# MCU_Interconnect_Rev1.net
KiCad netlist of a schematic drawn in Altium Designer
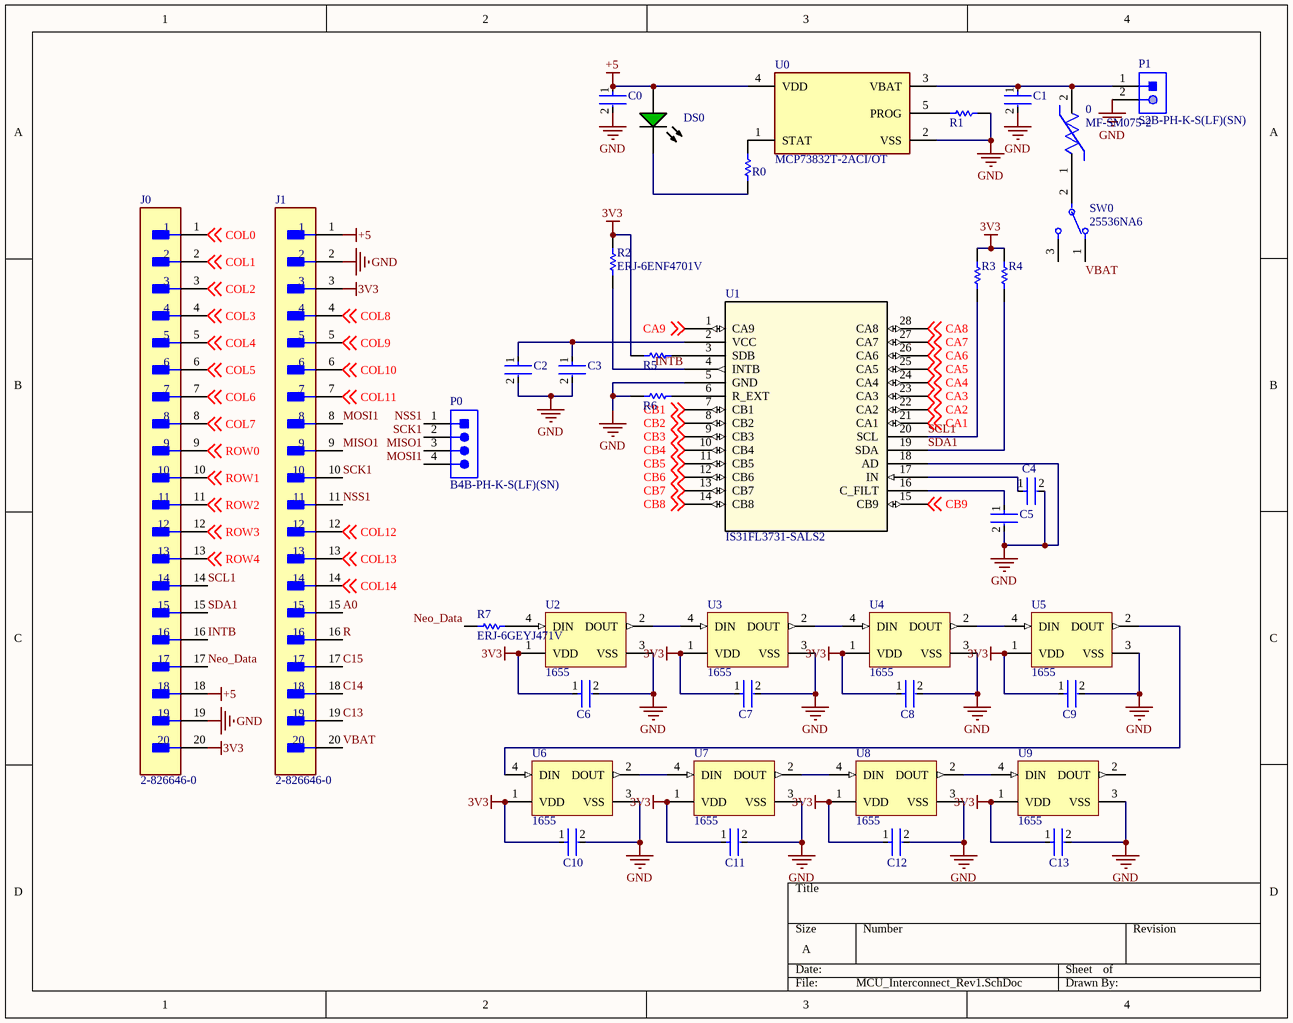
[diagram p0: MCU_Interconnect_Rev1.SchDoc]

(export (version "E")
  (design (tool "Eeschema 10.0.6"))
  (components
    (comp (ref "0")
      (value "MF-SM075-2")
      (footprint "FP-MF-SM075-MFG")
      (description "Polymeric PTC Resettable Fuse 30V 750mA Ih Surface Mount 2-SMD")
      (fields (field (name "MANUFACTURER") "Bourns Inc."))
      (libsource (lib "Altium Content Vault") (part "fdf083d5f6389a9a1c4e51137f46658"))
    )
    (comp (ref "C0")
      (value "GRM21BR71C475KE51L")
      (footprint "FP-GRM21B-0_15-IPC_C")
      (description "Chip Multilayer Ceramic Capacitors for General Purpose, 0805, 4.7uF, X7R, 15%, 10%, 16V")
      (fields (field (name "TOLERANCE") "10%"))
      (libsource (lib "Altium Content Vault") (part "b4654b650e69147ec39a6b967a45e02"))
    )
    (comp (ref "C1")
      (value "GRM21BR71C475KE51L")
      (footprint "FP-GRM21B-0_15-IPC_C")
      (description "Chip Multilayer Ceramic Capacitors for General Purpose, 0805, 4.7uF, X7R, 15%, 10%, 16V")
      (fields (field (name "TOLERANCE") "10%"))
      (libsource (lib "Altium Content Vault") (part "b4654b650e69147ec39a6b967a45e02"))
    )
    (comp (ref "C2")
      (value "GRM219R7YA105KA12D")
      (footprint "FP-GRM219-0_1-MFG")
      (description "Chip Multilayer Ceramic Capacitors for General Purpose, 0805, 1.0uF, X7R, 15%, 10%, 35V")
      (fields (field (name "TOLERANCE") "10%"))
      (libsource (lib "Altium Content Vault") (part "02cd4be3c70576c341d710602a673aa"))
    )
    (comp (ref "C3")
      (value "GRM21B7U1A104JA01L")
      (footprint "FP-GRM21B-0_1-IPC_B")
      (description "Chip Multilayer Ceramic Capacitors for General Purpose, 0805, 0.10uF, U2J, -750ppm/°C, 5%, 10V")
      (fields (field (name "TOLERANCE") "5%"))
      (libsource (lib "Altium Content Vault") (part "b4654b650e69147ec39a6b967a45e02"))
    )
    (comp (ref "C4")
      (value "GCM21BR71H224KA37L")
      (footprint "FP-GCM21B-0_15-IPC_C")
      (description "Ceramic Capacitor for Automotive 220nF ±10% 50VDC X7R 0805 Embossed T/R")
      (fields (field (name "TOLERANCE") "10%") (field (name "VOLTAGE") "50V"))
      (libsource (lib "Altium Content Vault") (part "02cd4be3c70576c341d710602a673aa"))
    )
    (comp (ref "C5")
      (value "GRM21B7U1A104JA01L")
      (footprint "FP-GRM21B-0_1-IPC_B")
      (description "Chip Multilayer Ceramic Capacitors for General Purpose, 0805, 0.10uF, U2J, -750ppm/°C, 5%, 10V")
      (fields (field (name "TOLERANCE") "5%"))
      (libsource (lib "Altium Content Vault") (part "b4654b650e69147ec39a6b967a45e02"))
    )
    (comp (ref "C6")
      (value "GRM21B7U1A104JA01L")
      (footprint "FP-GRM21B-0_1-IPC_B")
      (description "Chip Multilayer Ceramic Capacitors for General Purpose, 0805, 0.10uF, U2J, -750ppm/°C, 5%, 10V")
      (fields (field (name "TOLERANCE") "5%"))
      (libsource (lib "Altium Content Vault") (part "b4654b650e69147ec39a6b967a45e02"))
    )
    (comp (ref "C7")
      (value "GRM21B7U1A104JA01L")
      (footprint "FP-GRM21B-0_1-IPC_B")
      (description "Chip Multilayer Ceramic Capacitors for General Purpose, 0805, 0.10uF, U2J, -750ppm/°C, 5%, 10V")
      (fields (field (name "TOLERANCE") "5%"))
      (libsource (lib "Altium Content Vault") (part "b4654b650e69147ec39a6b967a45e02"))
    )
    (comp (ref "C8")
      (value "GRM21B7U1A104JA01L")
      (footprint "FP-GRM21B-0_1-IPC_B")
      (description "Chip Multilayer Ceramic Capacitors for General Purpose, 0805, 0.10uF, U2J, -750ppm/°C, 5%, 10V")
      (fields (field (name "TOLERANCE") "5%"))
      (libsource (lib "Altium Content Vault") (part "b4654b650e69147ec39a6b967a45e02"))
    )
    (comp (ref "C9")
      (value "GRM21B7U1A104JA01L")
      (footprint "FP-GRM21B-0_1-IPC_B")
      (description "Chip Multilayer Ceramic Capacitors for General Purpose, 0805, 0.10uF, U2J, -750ppm/°C, 5%, 10V")
      (fields (field (name "TOLERANCE") "5%"))
      (libsource (lib "Altium Content Vault") (part "b4654b650e69147ec39a6b967a45e02"))
    )
    (comp (ref "C10")
      (value "GRM21B7U1A104JA01L")
      (footprint "FP-GRM21B-0_1-IPC_B")
      (description "Chip Multilayer Ceramic Capacitors for General Purpose, 0805, 0.10uF, U2J, -750ppm/°C, 5%, 10V")
      (fields (field (name "TOLERANCE") "5%"))
      (libsource (lib "Altium Content Vault") (part "b4654b650e69147ec39a6b967a45e02"))
    )
    (comp (ref "C11")
      (value "GRM21B7U1A104JA01L")
      (footprint "FP-GRM21B-0_1-IPC_B")
      (description "Chip Multilayer Ceramic Capacitors for General Purpose, 0805, 0.10uF, U2J, -750ppm/°C, 5%, 10V")
      (fields (field (name "TOLERANCE") "5%"))
      (libsource (lib "Altium Content Vault") (part "b4654b650e69147ec39a6b967a45e02"))
    )
    (comp (ref "C12")
      (value "GRM21B7U1A104JA01L")
      (footprint "FP-GRM21B-0_1-IPC_B")
      (description "Chip Multilayer Ceramic Capacitors for General Purpose, 0805, 0.10uF, U2J, -750ppm/°C, 5%, 10V")
      (fields (field (name "TOLERANCE") "5%"))
      (libsource (lib "Altium Content Vault") (part "b4654b650e69147ec39a6b967a45e02"))
    )
    (comp (ref "C13")
      (value "GRM21B7U1A104JA01L")
      (footprint "FP-GRM21B-0_1-IPC_B")
      (description "Chip Multilayer Ceramic Capacitors for General Purpose, 0805, 0.10uF, U2J, -750ppm/°C, 5%, 10V")
      (fields (field (name "TOLERANCE") "5%"))
      (libsource (lib "Altium Content Vault") (part "b4654b650e69147ec39a6b967a45e02"))
    )
    (comp (ref "DS0")
      (value "LTST-C170KGKT")
      (footprint "LTST-LTST-C170KGKT-2_V")
      (description "Ultra Bright AlInGaP Chip LED, 75 mW, -55 to 85 degC, 2-Pin SMD (0805), RoHS, Tape and Reel")
      (fields (field (name "MANUFACTURER") "Lite-On"))
      (libsource (lib "Altium Content Vault") (part "LED-GREEN-KA-2"))
    )
    (comp (ref "J0")
      (value "2-826646-0")
      (footprint "FP-2-826646-0-MFG")
      (description "CONN HEADER VERT 20POS 2.54MM")
      (libsource (lib "Altium Content Vault") (part "09d5f2461bb0697fba3bd732061644e"))
    )
    (comp (ref "J1")
      (value "2-826646-0")
      (footprint "FP-2-826646-0-MFG")
      (description "CONN HEADER VERT 20POS 2.54MM")
      (libsource (lib "Altium Content Vault") (part "09d5f2461bb0697fba3bd732061644e"))
    )
    (comp (ref "P0")
      (value "B4B-PH-K-S(LF)(SN)")
      (footprint "JST-B4B-PH-K-S_V")
      (fields (field (name "MANUFACTURER") "JST"))
      (libsource (lib "Altium Content Vault") (part "CN-1P-M-R4"))
    )
    (comp (ref "P1")
      (value "S2B-PH-K-S(LF)(SN)")
      (footprint "JST-S2B-PH-K-S_V")
      (fields (field (name "TOLERANCE") "20%"))
      (libsource (lib "Altium Content Vault") (part "CN-1P-M-R2"))
    )
    (comp (ref "R0")
      (value "RC0805FR-07470RL")
      (footprint "RESC2013X60X35LL10T20")
      (description "Chip Resistor, 470 Ohm, +/- 1%, 125 mW, -55 to 155 degC, 0805 (2012 Metric), RoHS, Tape and Reel")
      (fields (field (name "MANUFACTURER") "Yageo"))
      (libsource (lib "Altium Content Vault") (part "RES-2"))
    )
    (comp (ref "R1")
      (value "ERJ-6ENF1001V")
      (footprint "RESC2013X70X40ML20T20")
      (description "Chip Resistor, 1 KOhm, +/- 1%, 0.125 W, -55 to 155 degC, 0805 (2012 Metric), RoHS, Tape and Reel")
      (fields (field (name "MANUFACTURER") "Panasonic"))
      (libsource (lib "Altium Content Vault") (part "RES-2"))
    )
    (comp (ref "R2")
      (value "ERJ-6ENF4701V")
      (footprint "RESC2013X70X40NL20T20")
      (description "Chip Resistor, 4.7 KOhm, +/- 1%, 0.125 W, -55 to 155 degC, 0805 (2012 Metric), RoHS, Tape and Reel")
      (fields (field (name "MANUFACTURER") "Panasonic"))
      (libsource (lib "Altium Content Vault") (part "RES-2"))
    )
    (comp (ref "R3")
      (value "ERJ-6ENF4701V")
      (footprint "RESC2013X70X40NL20T20")
      (description "Chip Resistor, 4.7 KOhm, +/- 1%, 0.125 W, -55 to 155 degC, 0805 (2012 Metric), RoHS, Tape and Reel")
      (fields (field (name "MANUFACTURER") "Panasonic"))
      (libsource (lib "Altium Content Vault") (part "RES-2"))
    )
    (comp (ref "R4")
      (value "ERJ-6ENF4701V")
      (footprint "RESC2013X70X40NL20T20")
      (description "Chip Resistor, 4.7 KOhm, +/- 1%, 0.125 W, -55 to 155 degC, 0805 (2012 Metric), RoHS, Tape and Reel")
      (fields (field (name "MANUFACTURER") "Panasonic"))
      (libsource (lib "Altium Content Vault") (part "RES-2"))
    )
    (comp (ref "R5")
      (value "ERJ-6ENF1003V")
      (footprint "RESC2013X70X40ML20T20")
      (description "100kOhm")
      (fields (field (name "MANUFACTURER") "Panasonic"))
      (libsource (lib "Altium Content Vault") (part "RES"))
    )
    (comp (ref "R6")
      (value "ERJ-6ENF1003V")
      (footprint "RESC2013X70X40ML20T20")
      (description "100kOhm")
      (fields (field (name "MANUFACTURER") "Panasonic"))
      (libsource (lib "Altium Content Vault") (part "RES"))
    )
    (comp (ref "R7")
      (value "ERJ-6GEYJ471V")
      (footprint "RESC2013X70X40LL20T20")
      (fields (field (name "MANUFACTURER") "Panasonic"))
      (libsource (lib "Altium Content Vault") (part "RES"))
    )
    (comp (ref "SW0")
      (value "25536NA6")
      (footprint "FP-25536NA6-0")
      (description "SWITCH SLIDE SPDT 4A 125V")
      (libsource (lib "Altium Content Vault") (part "52c419afdc2a387c7d548259a9aeefb"))
    )
    (comp (ref "U0")
      (value "MCP73832T-2ACI/OT")
      (footprint "FP-C04-091-OT-MFG")
      (description "IC LI-ION/LI-POLY CTRLR SOT23-5")
      (libsource (lib "Altium Content Vault") (part "61f5a3bb3429d9e0caadea342aa3b19"))
    )
    (comp (ref "U1")
      (value "IS31FL3731-SALS2")
      (footprint "SSOP-28_ISI")
      (description "No Description Available")
      (fields (field (name "COPYRIGHT") "Copyright (C) 2018 Accelerated Designs. All rights reserved"))
      (libsource (lib "IS31FL3731-SALS2") (part "IS31FL3731-SALS2"))
    )
    (comp (ref "U2")
      (value "1655")
      (footprint "ADA-RGB-1655_V")
      (fields (field (name "MANUFACTURER") "Adafruit-Industries-LLC"))
      (libsource (lib "Altium Content Vault") (part "ADA-RGB-1655-4"))
    )
    (comp (ref "U3")
      (value "1655")
      (footprint "ADA-RGB-1655_V")
      (fields (field (name "MANUFACTURER") "Adafruit-Industries-LLC"))
      (libsource (lib "Altium Content Vault") (part "ADA-RGB-1655-4"))
    )
    (comp (ref "U4")
      (value "1655")
      (footprint "ADA-RGB-1655_V")
      (fields (field (name "MANUFACTURER") "Adafruit-Industries-LLC"))
      (libsource (lib "Altium Content Vault") (part "ADA-RGB-1655-4"))
    )
    (comp (ref "U5")
      (value "1655")
      (footprint "ADA-RGB-1655_V")
      (fields (field (name "MANUFACTURER") "Adafruit-Industries-LLC"))
      (libsource (lib "Altium Content Vault") (part "ADA-RGB-1655-4"))
    )
    (comp (ref "U6")
      (value "1655")
      (footprint "ADA-RGB-1655_V")
      (fields (field (name "MANUFACTURER") "Adafruit-Industries-LLC"))
      (libsource (lib "Altium Content Vault") (part "ADA-RGB-1655-4"))
    )
    (comp (ref "U7")
      (value "1655")
      (footprint "ADA-RGB-1655_V")
      (fields (field (name "MANUFACTURER") "Adafruit-Industries-LLC"))
      (libsource (lib "Altium Content Vault") (part "ADA-RGB-1655-4"))
    )
    (comp (ref "U8")
      (value "1655")
      (footprint "ADA-RGB-1655_V")
      (fields (field (name "MANUFACTURER") "Adafruit-Industries-LLC"))
      (libsource (lib "Altium Content Vault") (part "ADA-RGB-1655-4"))
    )
    (comp (ref "U9")
      (value "1655")
      (footprint "ADA-RGB-1655_V")
      (fields (field (name "MANUFACTURER") "Adafruit-Industries-LLC"))
      (libsource (lib "Altium Content Vault") (part "ADA-RGB-1655-4"))
    )
  )
  (nets
    (net (code "1") (name "+5") (class "Default")
      (node (ref "C0") (pin "1") (pinfunction "1_1") (pintype "passive"))
      (node (ref "DS0") (pin "2") (pinfunction "A_2") (pintype "passive"))
      (node (ref "J0") (pin "18") (pinfunction "18_18") (pintype "passive"))
      (node (ref "J1") (pin "1") (pinfunction "1_1") (pintype "passive"))
      (node (ref "U0") (pin "4") (pinfunction "VDD_4") (pintype "power_in"))
    )
    (net (code "2") (name "/A0") (class "Default")
      (node (ref "J1") (pin "15") (pinfunction "15_15") (pintype "passive"))
    )
    (net (code "3") (name "/C13") (class "Default")
      (node (ref "J1") (pin "19") (pinfunction "19_19") (pintype "passive"))
    )
    (net (code "4") (name "/C14") (class "Default")
      (node (ref "J1") (pin "18") (pinfunction "18_18") (pintype "passive"))
    )
    (net (code "5") (name "/C15") (class "Default")
      (node (ref "J1") (pin "17") (pinfunction "17_17") (pintype "passive"))
    )
    (net (code "6") (name "/INTB") (class "Default")
      (node (ref "J0") (pin "16") (pinfunction "16_16") (pintype "passive"))
      (node (ref "R2") (pin "1") (pinfunction "1_1") (pintype "passive"))
      (node (ref "U1") (pin "4") (pinfunction "INTB_4") (pintype "output"))
    )
    (net (code "7") (name "/MISO1") (class "Default")
      (node (ref "J1") (pin "9") (pinfunction "9_9") (pintype "passive"))
      (node (ref "P0") (pin "3") (pinfunction "3_3") (pintype "passive"))
    )
    (net (code "8") (name "/MOSI1") (class "Default")
      (node (ref "J1") (pin "8") (pinfunction "8_8") (pintype "passive"))
      (node (ref "P0") (pin "4") (pinfunction "4_4") (pintype "passive"))
    )
    (net (code "9") (name "/NSS1") (class "Default")
      (node (ref "J1") (pin "11") (pinfunction "11_11") (pintype "passive"))
      (node (ref "P0") (pin "1") (pinfunction "1_1") (pintype "passive"))
    )
    (net (code "10") (name "/Neo_Data") (class "Default")
      (node (ref "J0") (pin "17") (pinfunction "17_17") (pintype "passive"))
      (node (ref "R7") (pin "1") (pinfunction "1_1") (pintype "passive"))
    )
    (net (code "11") (name "/R") (class "Default")
      (node (ref "J1") (pin "16") (pinfunction "16_16") (pintype "passive"))
    )
    (net (code "12") (name "/SCK1") (class "Default")
      (node (ref "J1") (pin "10") (pinfunction "10_10") (pintype "passive"))
      (node (ref "P0") (pin "2") (pinfunction "2_2") (pintype "passive"))
    )
    (net (code "13") (name "/SCL1") (class "Default")
      (node (ref "J0") (pin "14") (pinfunction "14_14") (pintype "passive"))
      (node (ref "R3") (pin "1") (pinfunction "1_1") (pintype "passive"))
      (node (ref "U1") (pin "20") (pinfunction "SCL_20") (pintype "passive"))
    )
    (net (code "14") (name "/SDA1") (class "Default")
      (node (ref "J0") (pin "15") (pinfunction "15_15") (pintype "passive"))
      (node (ref "R4") (pin "1") (pinfunction "1_1") (pintype "passive"))
      (node (ref "U1") (pin "19") (pinfunction "SDA_19") (pintype "passive"))
    )
    (net (code "15") (name "/VBAT") (class "Default")
      (node (ref "J1") (pin "20") (pinfunction "20_20") (pintype "passive"))
      (node (ref "SW0") (pin "1") (pinfunction "1_1") (pintype "passive"))
    )
    (net (code "16") (name "3V3") (class "Default")
      (node (ref "C10") (pin "1") (pinfunction "1_1") (pintype "passive"))
      (node (ref "C11") (pin "1") (pinfunction "1_1") (pintype "passive"))
      (node (ref "C12") (pin "1") (pinfunction "1_1") (pintype "passive"))
      (node (ref "C13") (pin "1") (pinfunction "1_1") (pintype "passive"))
      (node (ref "C6") (pin "1") (pinfunction "1_1") (pintype "passive"))
      (node (ref "C7") (pin "1") (pinfunction "1_1") (pintype "passive"))
      (node (ref "C8") (pin "1") (pinfunction "1_1") (pintype "passive"))
      (node (ref "C9") (pin "1") (pinfunction "1_1") (pintype "passive"))
      (node (ref "J0") (pin "20") (pinfunction "20_20") (pintype "passive"))
      (node (ref "J1") (pin "3") (pinfunction "3_3") (pintype "passive"))
      (node (ref "R2") (pin "2") (pinfunction "2_2") (pintype "passive"))
      (node (ref "R3") (pin "2") (pinfunction "2_2") (pintype "passive"))
      (node (ref "R4") (pin "2") (pinfunction "2_2") (pintype "passive"))
      (node (ref "R5") (pin "1") (pinfunction "1_1") (pintype "passive"))
      (node (ref "U2") (pin "1") (pinfunction "VDD_1") (pintype "power_in"))
      (node (ref "U3") (pin "1") (pinfunction "VDD_1") (pintype "power_in"))
      (node (ref "U4") (pin "1") (pinfunction "VDD_1") (pintype "power_in"))
      (node (ref "U5") (pin "1") (pinfunction "VDD_1") (pintype "power_in"))
      (node (ref "U6") (pin "1") (pinfunction "VDD_1") (pintype "power_in"))
      (node (ref "U7") (pin "1") (pinfunction "VDD_1") (pintype "power_in"))
      (node (ref "U8") (pin "1") (pinfunction "VDD_1") (pintype "power_in"))
      (node (ref "U9") (pin "1") (pinfunction "VDD_1") (pintype "power_in"))
    )
    (net (code "17") (name "CA1") (class "Default")
      (node (ref "U1") (pin "21") (pinfunction "CA1_21") (pintype "bidirectional"))
    )
    (net (code "18") (name "CA2") (class "Default")
      (node (ref "U1") (pin "22") (pinfunction "CA2_22") (pintype "bidirectional"))
    )
    (net (code "19") (name "CA3") (class "Default")
      (node (ref "U1") (pin "23") (pinfunction "CA3_23") (pintype "bidirectional"))
    )
    (net (code "20") (name "CA4") (class "Default")
      (node (ref "U1") (pin "24") (pinfunction "CA4_24") (pintype "bidirectional"))
    )
    (net (code "21") (name "CA5") (class "Default")
      (node (ref "U1") (pin "25") (pinfunction "CA5_25") (pintype "bidirectional"))
    )
    (net (code "22") (name "CA6") (class "Default")
      (node (ref "U1") (pin "26") (pinfunction "CA6_26") (pintype "bidirectional"))
    )
    (net (code "23") (name "CA7") (class "Default")
      (node (ref "U1") (pin "27") (pinfunction "CA7_27") (pintype "bidirectional"))
    )
    (net (code "24") (name "CA8") (class "Default")
      (node (ref "U1") (pin "28") (pinfunction "CA8_28") (pintype "bidirectional"))
    )
    (net (code "25") (name "CA9") (class "Default")
      (node (ref "U1") (pin "1") (pinfunction "CA9_1") (pintype "bidirectional"))
    )
    (net (code "26") (name "CB1") (class "Default")
      (node (ref "U1") (pin "7") (pinfunction "CB1_7") (pintype "bidirectional"))
    )
    (net (code "27") (name "CB2") (class "Default")
      (node (ref "U1") (pin "8") (pinfunction "CB2_8") (pintype "bidirectional"))
    )
    (net (code "28") (name "CB3") (class "Default")
      (node (ref "U1") (pin "9") (pinfunction "CB3_9") (pintype "bidirectional"))
    )
    (net (code "29") (name "CB4") (class "Default")
      (node (ref "U1") (pin "10") (pinfunction "CB4_10") (pintype "bidirectional"))
    )
    (net (code "30") (name "CB5") (class "Default")
      (node (ref "U1") (pin "11") (pinfunction "CB5_11") (pintype "bidirectional"))
    )
    (net (code "31") (name "CB6") (class "Default")
      (node (ref "U1") (pin "12") (pinfunction "CB6_12") (pintype "bidirectional"))
    )
    (net (code "32") (name "CB7") (class "Default")
      (node (ref "U1") (pin "13") (pinfunction "CB7_13") (pintype "bidirectional"))
    )
    (net (code "33") (name "CB8") (class "Default")
      (node (ref "U1") (pin "14") (pinfunction "CB8_14") (pintype "bidirectional"))
    )
    (net (code "34") (name "CB9") (class "Default")
      (node (ref "U1") (pin "15") (pinfunction "CB9_15") (pintype "bidirectional"))
    )
    (net (code "35") (name "COL0") (class "Default")
      (node (ref "J0") (pin "1") (pinfunction "1_1") (pintype "passive"))
    )
    (net (code "36") (name "COL1") (class "Default")
      (node (ref "J0") (pin "2") (pinfunction "2_2") (pintype "passive"))
    )
    (net (code "37") (name "COL2") (class "Default")
      (node (ref "J0") (pin "3") (pinfunction "3_3") (pintype "passive"))
    )
    (net (code "38") (name "COL3") (class "Default")
      (node (ref "J0") (pin "4") (pinfunction "4_4") (pintype "passive"))
    )
    (net (code "39") (name "COL4") (class "Default")
      (node (ref "J0") (pin "5") (pinfunction "5_5") (pintype "passive"))
    )
    (net (code "40") (name "COL5") (class "Default")
      (node (ref "J0") (pin "6") (pinfunction "6_6") (pintype "passive"))
    )
    (net (code "41") (name "COL6") (class "Default")
      (node (ref "J0") (pin "7") (pinfunction "7_7") (pintype "passive"))
    )
    (net (code "42") (name "COL7") (class "Default")
      (node (ref "J0") (pin "8") (pinfunction "8_8") (pintype "passive"))
    )
    (net (code "43") (name "COL8") (class "Default")
      (node (ref "J1") (pin "4") (pinfunction "4_4") (pintype "passive"))
    )
    (net (code "44") (name "COL9") (class "Default")
      (node (ref "J1") (pin "5") (pinfunction "5_5") (pintype "passive"))
    )
    (net (code "45") (name "COL10") (class "Default")
      (node (ref "J1") (pin "6") (pinfunction "6_6") (pintype "passive"))
    )
    (net (code "46") (name "COL11") (class "Default")
      (node (ref "J1") (pin "7") (pinfunction "7_7") (pintype "passive"))
    )
    (net (code "47") (name "COL12") (class "Default")
      (node (ref "J1") (pin "12") (pinfunction "12_12") (pintype "passive"))
    )
    (net (code "48") (name "COL13") (class "Default")
      (node (ref "J1") (pin "13") (pinfunction "13_13") (pintype "passive"))
    )
    (net (code "49") (name "COL14") (class "Default")
      (node (ref "J1") (pin "14") (pinfunction "14_14") (pintype "passive"))
    )
    (net (code "50") (name "GND") (class "Default")
      (node (ref "C0") (pin "2") (pinfunction "2_2") (pintype "passive"))
      (node (ref "C1") (pin "2") (pinfunction "2_2") (pintype "passive"))
      (node (ref "C10") (pin "2") (pinfunction "2_2") (pintype "passive"))
      (node (ref "C11") (pin "2") (pinfunction "2_2") (pintype "passive"))
      (node (ref "C12") (pin "2") (pinfunction "2_2") (pintype "passive"))
      (node (ref "C13") (pin "2") (pinfunction "2_2") (pintype "passive"))
      (node (ref "C2") (pin "2") (pinfunction "2_2") (pintype "passive"))
      (node (ref "C3") (pin "2") (pinfunction "2_2") (pintype "passive"))
      (node (ref "C4") (pin "2") (pinfunction "2_2") (pintype "passive"))
      (node (ref "C5") (pin "2") (pinfunction "2_2") (pintype "passive"))
      (node (ref "C6") (pin "2") (pinfunction "2_2") (pintype "passive"))
      (node (ref "C7") (pin "2") (pinfunction "2_2") (pintype "passive"))
      (node (ref "C8") (pin "2") (pinfunction "2_2") (pintype "passive"))
      (node (ref "C9") (pin "2") (pinfunction "2_2") (pintype "passive"))
      (node (ref "J0") (pin "19") (pinfunction "19_19") (pintype "passive"))
      (node (ref "J1") (pin "2") (pinfunction "2_2") (pintype "passive"))
      (node (ref "P1") (pin "2") (pinfunction "2_2") (pintype "passive"))
      (node (ref "R1") (pin "1") (pinfunction "1_1") (pintype "passive"))
      (node (ref "R6") (pin "1") (pinfunction "1_1") (pintype "passive"))
      (node (ref "U0") (pin "2") (pinfunction "VSS_2") (pintype "power_in"))
      (node (ref "U1") (pin "18") (pinfunction "AD_18") (pintype "passive"))
      (node (ref "U1") (pin "5") (pinfunction "GND_5") (pintype "passive"))
      (node (ref "U2") (pin "3") (pinfunction "VSS_3") (pintype "power_in"))
      (node (ref "U3") (pin "3") (pinfunction "VSS_3") (pintype "power_in"))
      (node (ref "U4") (pin "3") (pinfunction "VSS_3") (pintype "power_in"))
      (node (ref "U5") (pin "3") (pinfunction "VSS_3") (pintype "power_in"))
      (node (ref "U6") (pin "3") (pinfunction "VSS_3") (pintype "power_in"))
      (node (ref "U7") (pin "3") (pinfunction "VSS_3") (pintype "power_in"))
      (node (ref "U8") (pin "3") (pinfunction "VSS_3") (pintype "power_in"))
      (node (ref "U9") (pin "3") (pinfunction "VSS_3") (pintype "power_in"))
    )
    (net (code "51") (name "Net-(0-Pad1)") (class "Default")
      (node (ref "0") (pin "1") (pinfunction "1_1") (pintype "passive"))
      (node (ref "SW0") (pin "2") (pinfunction "2_2") (pintype "passive"))
    )
    (net (code "52") (name "Net-(DS0-K)") (class "Default")
      (node (ref "DS0") (pin "1") (pinfunction "K_1") (pintype "passive"))
      (node (ref "R0") (pin "1") (pinfunction "1_1") (pintype "passive"))
    )
    (net (code "53") (name "Net-(U0-PROG)") (class "Default")
      (node (ref "R1") (pin "2") (pinfunction "2_2") (pintype "passive"))
      (node (ref "U0") (pin "5") (pinfunction "PROG_5") (pintype "passive"))
    )
    (net (code "54") (name "Net-(U0-STAT)") (class "Default")
      (node (ref "R0") (pin "2") (pinfunction "2_2") (pintype "passive"))
      (node (ref "U0") (pin "1") (pinfunction "STAT_1") (pintype "passive"))
    )
    (net (code "55") (name "Net-(U0-VBAT)") (class "Default")
      (node (ref "0") (pin "2") (pinfunction "2_2") (pintype "passive"))
      (node (ref "C1") (pin "1") (pinfunction "1_1") (pintype "passive"))
      (node (ref "P1") (pin "1") (pinfunction "1_1") (pintype "passive"))
      (node (ref "U0") (pin "3") (pinfunction "VBAT_3") (pintype "power_in"))
    )
    (net (code "56") (name "Net-(U1-C_FILT)") (class "Default")
      (node (ref "C5") (pin "1") (pinfunction "1_1") (pintype "passive"))
      (node (ref "U1") (pin "16") (pinfunction "C_FILT_16") (pintype "passive"))
    )
    (net (code "57") (name "Net-(U1-IN)") (class "Default")
      (node (ref "C4") (pin "1") (pinfunction "1_1") (pintype "passive"))
      (node (ref "U1") (pin "17") (pinfunction "IN_17") (pintype "input"))
    )
    (net (code "58") (name "Net-(U1-R_EXT)") (class "Default")
      (node (ref "R6") (pin "2") (pinfunction "2_2") (pintype "passive"))
      (node (ref "U1") (pin "6") (pinfunction "R_EXT_6") (pintype "passive"))
    )
    (net (code "59") (name "Net-(U1-SDB)") (class "Default")
      (node (ref "R5") (pin "2") (pinfunction "2_2") (pintype "passive"))
      (node (ref "U1") (pin "3") (pinfunction "SDB_3") (pintype "passive"))
    )
    (net (code "60") (name "Net-(U1-VCC)") (class "Default")
      (node (ref "C2") (pin "1") (pinfunction "1_1") (pintype "passive"))
      (node (ref "C3") (pin "1") (pinfunction "1_1") (pintype "passive"))
      (node (ref "U1") (pin "2") (pinfunction "VCC_2") (pintype "power_in"))
    )
    (net (code "61") (name "Net-(U2-DIN)") (class "Default")
      (node (ref "R7") (pin "2") (pinfunction "2_2") (pintype "passive"))
      (node (ref "U2") (pin "4") (pinfunction "DIN_4") (pintype "input"))
    )
    (net (code "62") (name "Net-(U2-DOUT)") (class "Default")
      (node (ref "U2") (pin "2") (pinfunction "DOUT_2") (pintype "output"))
      (node (ref "U3") (pin "4") (pinfunction "DIN_4") (pintype "input"))
    )
    (net (code "63") (name "Net-(U3-DOUT)") (class "Default")
      (node (ref "U3") (pin "2") (pinfunction "DOUT_2") (pintype "output"))
      (node (ref "U4") (pin "4") (pinfunction "DIN_4") (pintype "input"))
    )
    (net (code "64") (name "Net-(U4-DOUT)") (class "Default")
      (node (ref "U4") (pin "2") (pinfunction "DOUT_2") (pintype "output"))
      (node (ref "U5") (pin "4") (pinfunction "DIN_4") (pintype "input"))
    )
    (net (code "65") (name "Net-(U5-DOUT)") (class "Default")
      (node (ref "U5") (pin "2") (pinfunction "DOUT_2") (pintype "output"))
      (node (ref "U6") (pin "4") (pinfunction "DIN_4") (pintype "input"))
    )
    (net (code "66") (name "Net-(U6-DOUT)") (class "Default")
      (node (ref "U6") (pin "2") (pinfunction "DOUT_2") (pintype "output"))
      (node (ref "U7") (pin "4") (pinfunction "DIN_4") (pintype "input"))
    )
    (net (code "67") (name "Net-(U7-DOUT)") (class "Default")
      (node (ref "U7") (pin "2") (pinfunction "DOUT_2") (pintype "output"))
      (node (ref "U8") (pin "4") (pinfunction "DIN_4") (pintype "input"))
    )
    (net (code "68") (name "Net-(U8-DOUT)") (class "Default")
      (node (ref "U8") (pin "2") (pinfunction "DOUT_2") (pintype "output"))
      (node (ref "U9") (pin "4") (pinfunction "DIN_4") (pintype "input"))
    )
    (net (code "69") (name "ROW0") (class "Default")
      (node (ref "J0") (pin "9") (pinfunction "9_9") (pintype "passive"))
    )
    (net (code "70") (name "ROW1") (class "Default")
      (node (ref "J0") (pin "10") (pinfunction "10_10") (pintype "passive"))
    )
    (net (code "71") (name "ROW2") (class "Default")
      (node (ref "J0") (pin "11") (pinfunction "11_11") (pintype "passive"))
    )
    (net (code "72") (name "ROW3") (class "Default")
      (node (ref "J0") (pin "12") (pinfunction "12_12") (pintype "passive"))
    )
    (net (code "73") (name "ROW4") (class "Default")
      (node (ref "J0") (pin "13") (pinfunction "13_13") (pintype "passive"))
    )
    (net (code "74") (name "unconnected-(SW0-Pad3)") (class "Default")
      (node (ref "SW0") (pin "3") (pinfunction "3_3") (pintype "passive"))
    )
    (net (code "75") (name "unconnected-(U9-DOUT-Pad2)") (class "Default")
      (node (ref "U9") (pin "2") (pinfunction "DOUT_2") (pintype "output"))
    )
  )
)
